# 96kHz_LPF.net
KiCad netlist of a schematic drawn in Altium Designer
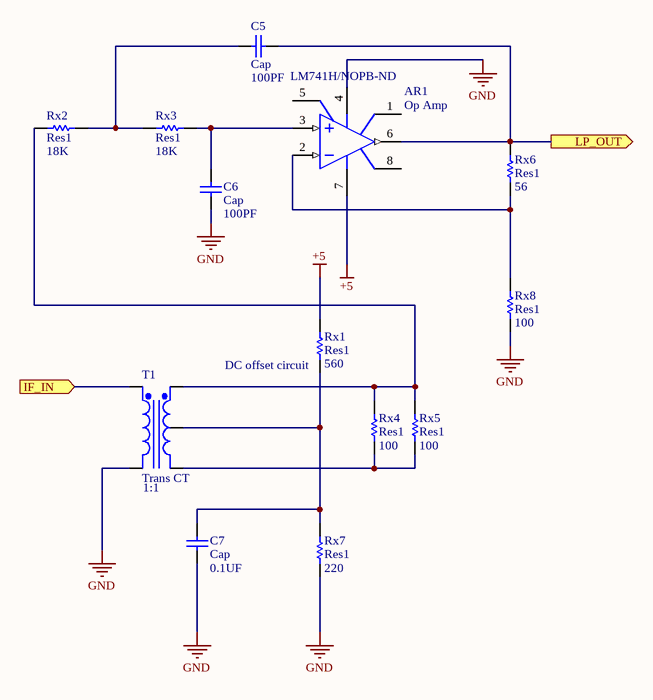
[diagram p0: 96kHz_LPF.SchDoc]

(export (version "E")
  (design (tool "Eeschema 10.0.6"))
  (components
    (comp (ref "AR1")
      (value "Op Amp")
      (footprint "H-08A")
      (description "FET Operational Amplifier")
      (fields
        (field (name "SUPPLIER PART NUMBER 1") "LM741H/NOPB-ND")
        (field (name "PUBLISHER") "Altium Limited")
      )
      (libsource (lib "Miscellaneous Devices") (part "Op Amp"))
    )
    (comp (ref "C5")
      (value "Cap")
      (footprint "RADIAL-0.1")
      (description "Capacitor")
      (fields
        (field (name "ALTIUM_VALUE") "100PF")
        (field (name "MANUFACTURER PART NUMBER") "K101K15C0GF53L2")
        (field (name "PUBLISHER") "Altium Limited")
      )
      (libsource (lib "ECE295-Capacitors-TH") (part "CAP CER 100PF 50V C0G/NP0 RADIAL"))
    )
    (comp (ref "C6")
      (value "Cap")
      (footprint "RADIAL-0.1")
      (description "Capacitor")
      (fields
        (field (name "ALTIUM_VALUE") "100PF")
        (field (name "MANUFACTURER PART NUMBER") "K101K15C0GF53L2")
        (field (name "PUBLISHER") "Altium Limited")
      )
      (libsource (lib "ECE295-Capacitors-TH") (part "CAP CER 100PF 50V C0G/NP0 RADIAL"))
    )
    (comp (ref "C7")
      (value "Cap")
      (footprint "RADIAL-0.1")
      (description "Capacitor")
      (fields
        (field (name "ALTIUM_VALUE") "0.1UF")
        (field (name "MANUFACTURER PART NUMBER") "K104M15X7RF5TH5")
        (field (name "PUBLISHER") "Altium Limited")
      )
      (libsource (lib "ECE295-Capacitors-TH") (part "CAP CER 0.1UF 50V X7R RADIAL"))
    )
    (comp (ref "Rx1")
      (value "Res1")
      (footprint "AXIAL-0.1-RES")
      (description "Resistor")
      (fields
        (field (name "ALTIUM_VALUE") "560")
        (field (name "MANUFACTURER PART NUMBER") "CFR-25JB-52-560R")
        (field (name "TOLERANCE") "0.05")
        (field (name "PUBLISHER") "Altium Limited")
      )
      (libsource (lib "ECE295-Resistors-TH") (part "RES 560 OHM 5% 1/4W AXIAL"))
    )
    (comp (ref "Rx2")
      (value "Res1")
      (footprint "AXIAL-0.1-RES")
      (description "Resistor")
      (fields
        (field (name "ALTIUM_VALUE") "18K")
        (field (name "MANUFACTURER PART NUMBER") "CFR-25JB-52-18K")
        (field (name "TOLERANCE") "0.05")
        (field (name "PUBLISHER") "Altium Limited")
      )
      (libsource (lib "ECE295-Resistors-TH") (part "RES 18K OHM 5% 1/4W AXIAL"))
    )
    (comp (ref "Rx3")
      (value "Res1")
      (footprint "AXIAL-0.1-RES")
      (description "Resistor")
      (fields
        (field (name "ALTIUM_VALUE") "18K")
        (field (name "MANUFACTURER PART NUMBER") "CFR-25JB-52-18K")
        (field (name "TOLERANCE") "0.05")
        (field (name "PUBLISHER") "Altium Limited")
      )
      (libsource (lib "ECE295-Resistors-TH") (part "RES 18K OHM 5% 1/4W AXIAL"))
    )
    (comp (ref "Rx4")
      (value "Res1")
      (footprint "AXIAL-0.1-RES")
      (description "Resistor")
      (fields
        (field (name "ALTIUM_VALUE") "100")
        (field (name "MANUFACTURER PART NUMBER") "CFR-25JB-52-100R")
        (field (name "TOLERANCE") "0.05")
        (field (name "PUBLISHER") "Altium Limited")
      )
      (libsource (lib "ECE295-Resistors-TH") (part "RES 100 OHM 5% 1/4W AXIAL"))
    )
    (comp (ref "Rx5")
      (value "Res1")
      (footprint "AXIAL-0.1-RES")
      (description "Resistor")
      (fields
        (field (name "ALTIUM_VALUE") "100")
        (field (name "MANUFACTURER PART NUMBER") "CFR-25JB-52-100R")
        (field (name "TOLERANCE") "0.05")
        (field (name "PUBLISHER") "Altium Limited")
      )
      (libsource (lib "ECE295-Resistors-TH") (part "RES 100 OHM 5% 1/4W AXIAL"))
    )
    (comp (ref "Rx6")
      (value "Res1")
      (footprint "AXIAL-0.1-RES")
      (description "Resistor")
      (fields
        (field (name "ALTIUM_VALUE") "56")
        (field (name "MANUFACTURER PART NUMBER") "CFR-25JB-52-56R")
        (field (name "TOLERANCE") "0.05")
        (field (name "PUBLISHER") "Altium Limited")
      )
      (libsource (lib "ECE295-Resistors-TH") (part "RES 56 OHM 5% 1/4W AXIAL"))
    )
    (comp (ref "Rx7")
      (value "Res1")
      (footprint "AXIAL-0.1-RES")
      (description "Resistor")
      (fields
        (field (name "ALTIUM_VALUE") "220")
        (field (name "MANUFACTURER PART NUMBER") "CFR-25JB-52-220R")
        (field (name "TOLERANCE") "0.05")
        (field (name "PUBLISHER") "Altium Limited")
      )
      (libsource (lib "ECE295-Resistors-TH") (part "RES 220 OHM 5% 1/4W AXIAL"))
    )
    (comp (ref "Rx8")
      (value "Res1")
      (footprint "AXIAL-0.1-RES")
      (description "Resistor")
      (fields
        (field (name "ALTIUM_VALUE") "100")
        (field (name "MANUFACTURER PART NUMBER") "CFR-25JB-52-100R")
        (field (name "TOLERANCE") "0.05")
        (field (name "PUBLISHER") "Altium Limited")
      )
      (libsource (lib "ECE295-Resistors-TH") (part "RES 100 OHM 5% 1/4W AXIAL"))
    )
    (comp (ref "T1")
      (value "Trans CT")
      (footprint "BIFILAR-2402")
      (description "Center-Tapped Transformer (Coupled Inductor Model)")
      (fields (field (name "PUBLISHER") "Altium Limited"))
      (libsource (lib "ECE295-Other") (part "Centre-tapped transformer wound on a binocular core"))
    )
  )
  (nets
    (net (code "1") (name "+5") (class "Default")
      (node (ref "AR1") (pin "7") (pinfunction "V+_7") (pintype "power_in"))
      (node (ref "Rx1") (pin "2") (pinfunction "2_2") (pintype "passive"))
    )
    (net (code "2") (name "/IF_IN") (class "Default")
      (node (ref "T1") (pin "4") (pinfunction "Pri+_4") (pintype "passive"))
    )
    (net (code "3") (name "/LP_OUT") (class "Default")
      (node (ref "AR1") (pin "6") (pinfunction "OUT_6") (pintype "output"))
      (node (ref "C5") (pin "2") (pinfunction "2_2") (pintype "passive"))
      (node (ref "Rx6") (pin "2") (pinfunction "2_2") (pintype "passive"))
    )
    (net (code "4") (name "GND") (class "Default")
      (node (ref "AR1") (pin "4") (pinfunction "V-_4") (pintype "power_in"))
      (node (ref "C6") (pin "1") (pinfunction "1_1") (pintype "passive"))
      (node (ref "C7") (pin "1") (pinfunction "1_1") (pintype "passive"))
      (node (ref "Rx7") (pin "1") (pinfunction "1_1") (pintype "passive"))
      (node (ref "Rx8") (pin "1") (pinfunction "1_1") (pintype "passive"))
      (node (ref "T1") (pin "5") (pinfunction "Pri-_5") (pintype "passive"))
    )
    (net (code "5") (name "Net-(AR1-IN+)") (class "Default")
      (node (ref "AR1") (pin "3") (pinfunction "IN+_3") (pintype "input"))
      (node (ref "C6") (pin "2") (pinfunction "2_2") (pintype "passive"))
      (node (ref "Rx3") (pin "2") (pinfunction "2_2") (pintype "passive"))
    )
    (net (code "6") (name "Net-(AR1-IN-)") (class "Default")
      (node (ref "AR1") (pin "2") (pinfunction "IN-_2") (pintype "input"))
      (node (ref "Rx6") (pin "1") (pinfunction "1_1") (pintype "passive"))
      (node (ref "Rx8") (pin "2") (pinfunction "2_2") (pintype "passive"))
    )
    (net (code "7") (name "Net-(C5-Pad1)") (class "Default")
      (node (ref "C5") (pin "1") (pinfunction "1_1") (pintype "passive"))
      (node (ref "Rx2") (pin "2") (pinfunction "2_2") (pintype "passive"))
      (node (ref "Rx3") (pin "1") (pinfunction "1_1") (pintype "passive"))
    )
    (net (code "8") (name "Net-(T1-Sec+)") (class "Default")
      (node (ref "Rx2") (pin "1") (pinfunction "1_1") (pintype "passive"))
      (node (ref "Rx4") (pin "2") (pinfunction "2_2") (pintype "passive"))
      (node (ref "Rx5") (pin "2") (pinfunction "2_2") (pintype "passive"))
      (node (ref "T1") (pin "1") (pinfunction "Sec+_1") (pintype "passive"))
    )
    (net (code "9") (name "Net-(T1-Sec-)") (class "Default")
      (node (ref "Rx4") (pin "1") (pinfunction "1_1") (pintype "passive"))
      (node (ref "Rx5") (pin "1") (pinfunction "1_1") (pintype "passive"))
      (node (ref "T1") (pin "3") (pinfunction "Sec-_3") (pintype "passive"))
    )
    (net (code "10") (name "Net-(T1-SecCT)") (class "Default")
      (node (ref "C7") (pin "2") (pinfunction "2_2") (pintype "passive"))
      (node (ref "Rx1") (pin "1") (pinfunction "1_1") (pintype "passive"))
      (node (ref "Rx7") (pin "2") (pinfunction "2_2") (pintype "passive"))
      (node (ref "T1") (pin "2") (pinfunction "SecCT_2") (pintype "passive"))
    )
    (net (code "11") (name "unconnected-(AR1-OS_NUL-Pad1)") (class "Default")
      (node (ref "AR1") (pin "1") (pinfunction "OS_NUL_1") (pintype "passive"))
    )
    (net (code "12") (name "unconnected-(AR1-OS_NUL-Pad5)") (class "Default")
      (node (ref "AR1") (pin "5") (pinfunction "OS_NUL_5") (pintype "passive"))
    )
    (net (code "13") (name "unconnected-(AR1-TAB-Pad8)") (class "Default")
      (node (ref "AR1") (pin "8") (pinfunction "TAB_8") (pintype "passive"))
    )
  )
)
